# Posibus_proto.net
KiCad netlist of a schematic drawn in EAGLE
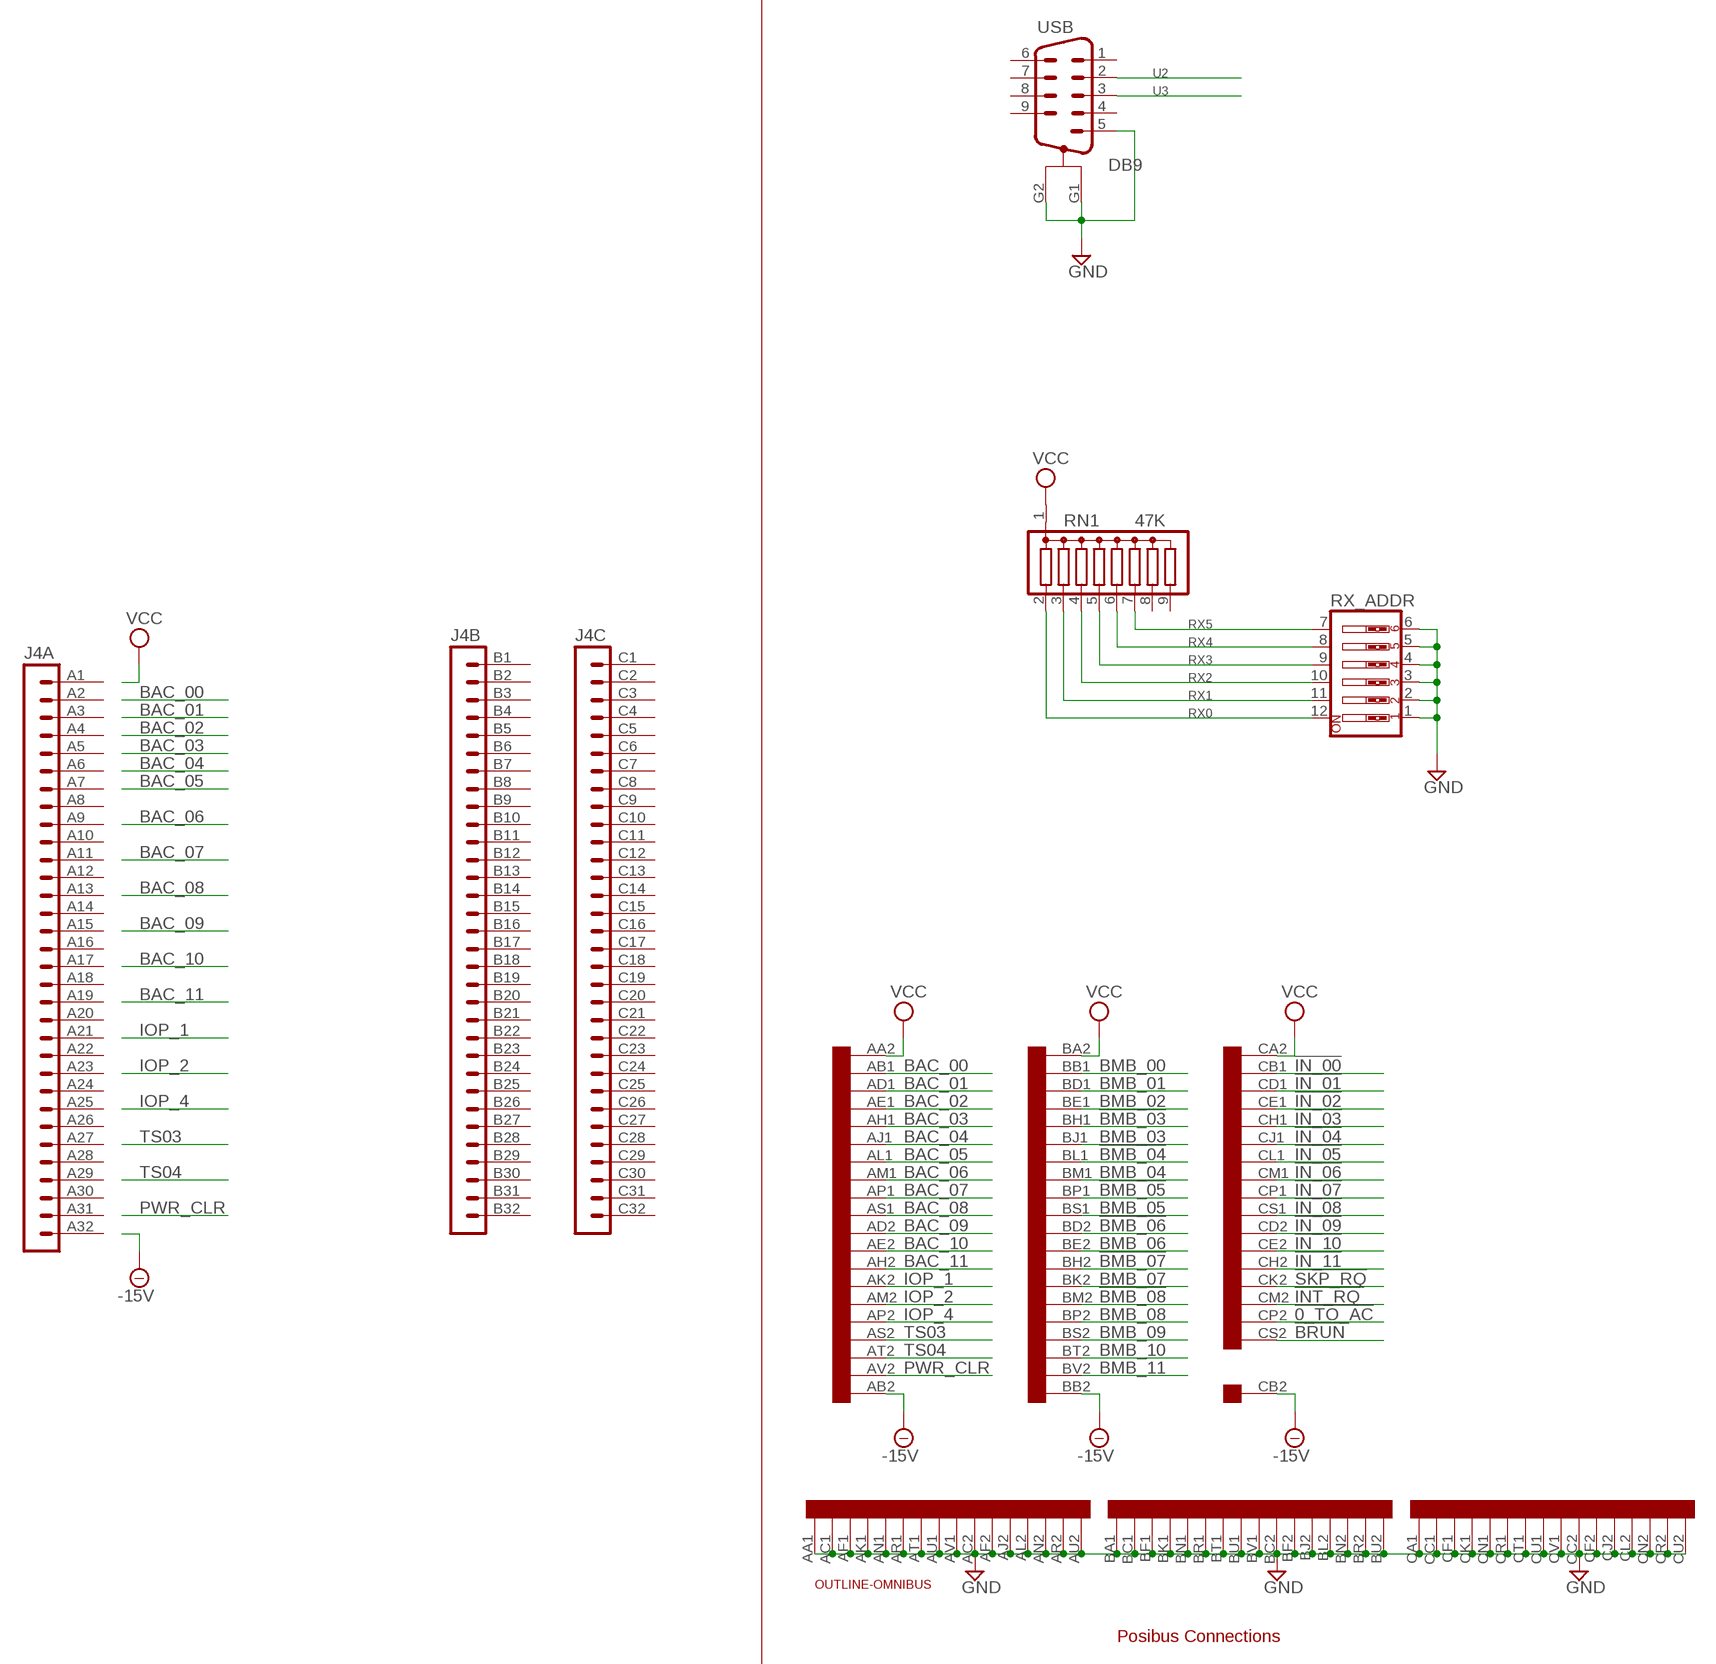
[diagram p0: schematic, sheet 1, part 1 of 2]
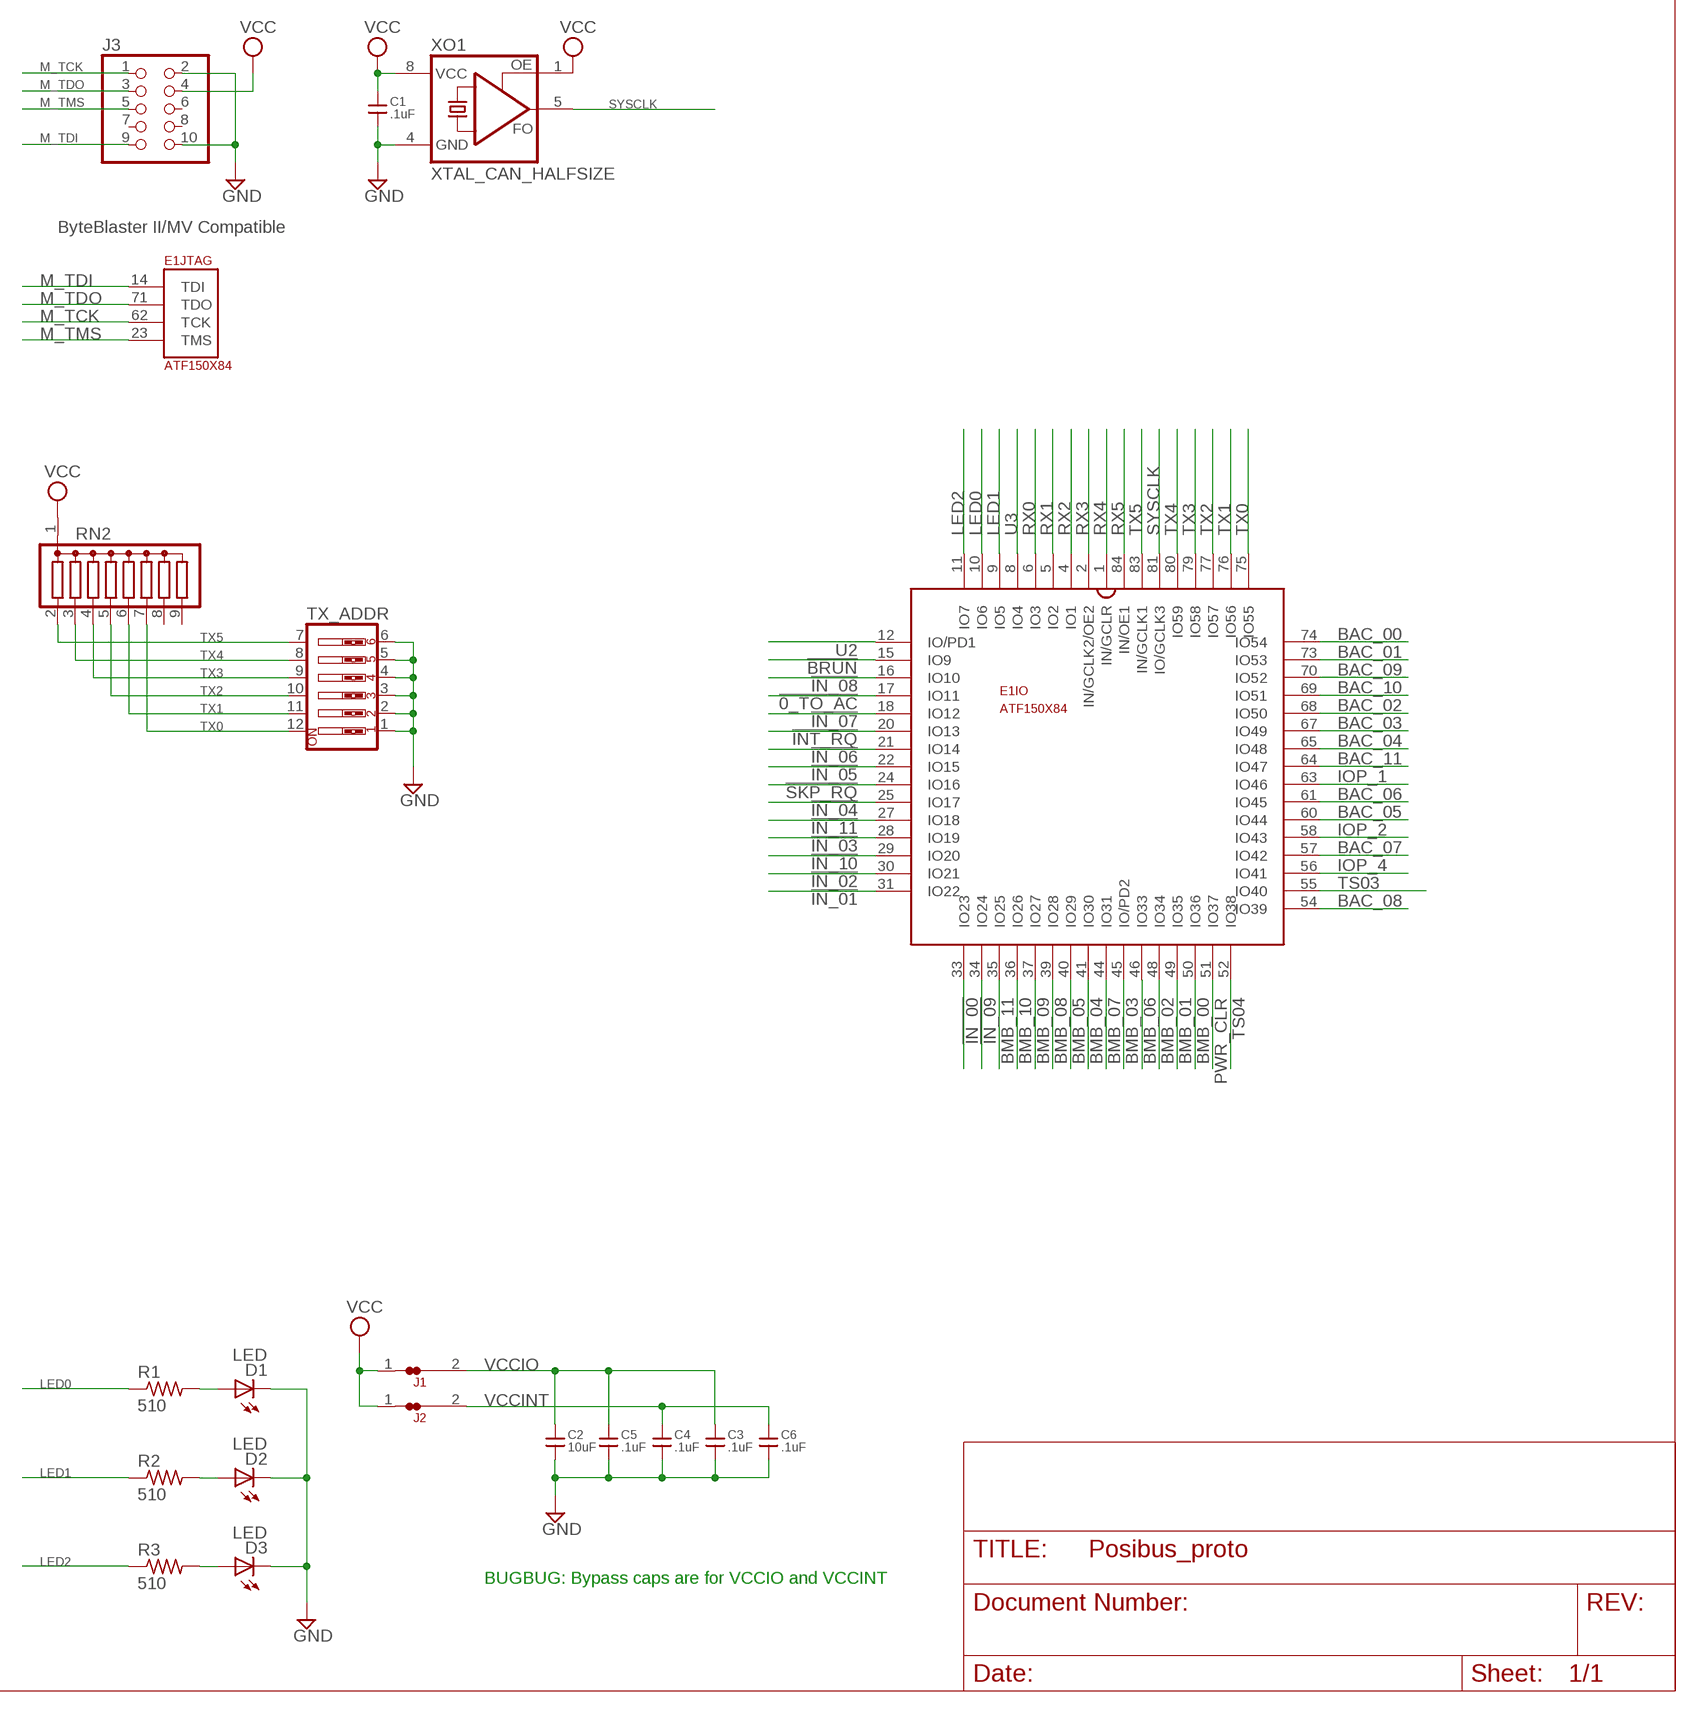
[diagram p1: schematic, sheet 1, part 2 of 2]

(export (version "E")
  (design (tool "Eeschema 10.0.6"))
  (components
    (comp (ref "C1")
      (value ".1uF")
      (footprint "eagle-import:C_TH_5MM")
      (libsource (lib "eagle-import") (part "C_US"))
    )
    (comp (ref "C2")
      (value "10uF")
      (footprint "eagle-import:C_TH_5MM")
      (libsource (lib "eagle-import") (part "C_US"))
    )
    (comp (ref "C3")
      (value ".1uF")
      (footprint "eagle-import:C_TH_5MM")
      (libsource (lib "eagle-import") (part "C_US"))
    )
    (comp (ref "C4")
      (value ".1uF")
      (footprint "eagle-import:C_TH_5MM")
      (libsource (lib "eagle-import") (part "C_US"))
    )
    (comp (ref "C5")
      (value ".1uF")
      (footprint "eagle-import:C_TH_5MM")
      (libsource (lib "eagle-import") (part "C_US"))
    )
    (comp (ref "C6")
      (value ".1uF")
      (footprint "eagle-import:C_TH_5MM")
      (libsource (lib "eagle-import") (part "C_US"))
    )
    (comp (ref "D1")
      (value "LED")
      (footprint "eagle-import:LED_TH_3MM")
      (libsource (lib "eagle-import") (part "LED"))
    )
    (comp (ref "D2")
      (value "LED")
      (footprint "eagle-import:LED_TH_3MM")
      (libsource (lib "eagle-import") (part "LED"))
    )
    (comp (ref "D3")
      (value "LED")
      (footprint "eagle-import:LED_TH_3MM")
      (libsource (lib "eagle-import") (part "LED"))
    )
    (comp (ref "E1")
      (value "ATF150X84")
      (footprint "eagle-import:S84")
      (libsource (lib "eagle-import") (part "ATF150X84"))
    )
    (comp (ref "J1")
      (value "JUMPER-NC1")
      (footprint "eagle-import:NC1")
      (libsource (lib "eagle-import") (part "JUMPER-NC1"))
    )
    (comp (ref "J2")
      (value "JUMPER-NC1")
      (footprint "eagle-import:NC1")
      (libsource (lib "eagle-import") (part "JUMPER-NC1"))
    )
    (comp (ref "J3")
      (value "HDR_2X5\"")
      (footprint "eagle-import:HDR_2X5")
      (libsource (lib "eagle-import") (part "HDR_2X5{dblquote}"))
    )
    (comp (ref "J4")
      (value "VG96-3B")
      (footprint "eagle-import:VG96B")
      (libsource (lib "eagle-import") (part "VG96-3B"))
    )
    (comp (ref "R1")
      (value "510")
      (footprint "eagle-import:R_204_7")
      (libsource (lib "eagle-import") (part "R_US"))
    )
    (comp (ref "R2")
      (value "510")
      (footprint "eagle-import:R_204_7")
      (libsource (lib "eagle-import") (part "R_US"))
    )
    (comp (ref "R3")
      (value "510")
      (footprint "eagle-import:R_204_7")
      (libsource (lib "eagle-import") (part "R_US"))
    )
    (comp (ref "RN1")
      (value "47K")
      (footprint "eagle-import:SIL9")
      (libsource (lib "eagle-import") (part "G08R"))
    )
    (comp (ref "RN2")
      (value "G08R")
      (footprint "eagle-import:SIL9")
      (libsource (lib "eagle-import") (part "G08R"))
    )
    (comp (ref "RX_ADDR")
      (value "SW_DIP-6")
      (footprint "eagle-import:EDG-06")
      (libsource (lib "eagle-import") (part "SW_DIP-6"))
    )
    (comp (ref "TX_ADDR")
      (value "SW_DIP-6")
      (footprint "eagle-import:EDG-06")
      (libsource (lib "eagle-import") (part "SW_DIP-6"))
    )
    (comp (ref "U$1")
      (value "QUAD")
      (footprint "eagle-import:EDGE-CON8")
      (libsource (lib "eagle-import") (part "QUAD"))
    )
    (comp (ref "U$2")
      (value "OUTLINE-OMNIBUS")
      (footprint "eagle-import:OMNIBUS")
      (libsource (lib "eagle-import") (part "OUTLINE-OMNIBUS"))
    )
    (comp (ref "USB")
      (value "DB9")
      (footprint "eagle-import:AMP_DB-9RA")
      (fields (field (name "MANF") "TE/AMP"))
      (libsource (lib "eagle-import") (part "DB9"))
    )
    (comp (ref "XO1")
      (value "XTAL_CAN_HALFSIZE")
      (footprint "eagle-import:XTAL_CAN_HALFSIZE")
      (libsource (lib "eagle-import") (part "XTAL_CAN_HALFSIZE"))
    )
  )
  (nets
    (net (code "1") (name "-15V") (class "Default")
      (node (ref "U$1") (pin "AB2") (pinfunction "1_AB2") (pintype "bidirectional"))
      (node (ref "U$1") (pin "BB2") (pinfunction "1_BB2") (pintype "bidirectional"))
      (node (ref "U$1") (pin "CB2") (pinfunction "1_CB2") (pintype "bidirectional"))
    )
    (net (code "2") (name "/BAC_00") (class "Default")
      (node (ref "E1") (pin "74") (pinfunction "IO54_74") (pintype "bidirectional"))
      (node (ref "U$1") (pin "AB1") (pinfunction "1_AB1") (pintype "bidirectional"))
    )
    (net (code "3") (name "/BAC_01") (class "Default")
      (node (ref "E1") (pin "73") (pinfunction "IO53_73") (pintype "bidirectional"))
      (node (ref "U$1") (pin "AD1") (pinfunction "1_AD1") (pintype "bidirectional"))
    )
    (net (code "4") (name "/BAC_02") (class "Default")
      (node (ref "E1") (pin "68") (pinfunction "IO50_68") (pintype "bidirectional"))
      (node (ref "U$1") (pin "AE1") (pinfunction "1_AE1") (pintype "bidirectional"))
    )
    (net (code "5") (name "/BAC_03") (class "Default")
      (node (ref "E1") (pin "67") (pinfunction "IO49_67") (pintype "bidirectional"))
      (node (ref "U$1") (pin "AH1") (pinfunction "1_AH1") (pintype "bidirectional"))
    )
    (net (code "6") (name "/BAC_04") (class "Default")
      (node (ref "E1") (pin "65") (pinfunction "IO48_65") (pintype "bidirectional"))
      (node (ref "U$1") (pin "AJ1") (pinfunction "1_AJ1") (pintype "bidirectional"))
    )
    (net (code "7") (name "/BAC_05") (class "Default")
      (node (ref "E1") (pin "60") (pinfunction "IO44_60") (pintype "bidirectional"))
      (node (ref "U$1") (pin "AL1") (pinfunction "1_AL1") (pintype "bidirectional"))
    )
    (net (code "8") (name "/BAC_06") (class "Default")
      (node (ref "E1") (pin "61") (pinfunction "IO45_61") (pintype "bidirectional"))
      (node (ref "U$1") (pin "AM1") (pinfunction "1_AM1") (pintype "bidirectional"))
    )
    (net (code "9") (name "/BAC_07") (class "Default")
      (node (ref "E1") (pin "57") (pinfunction "IO42_57") (pintype "bidirectional"))
      (node (ref "U$1") (pin "AP1") (pinfunction "1_AP1") (pintype "bidirectional"))
    )
    (net (code "10") (name "/BAC_08") (class "Default")
      (node (ref "E1") (pin "54") (pinfunction "IO39_54") (pintype "bidirectional"))
      (node (ref "U$1") (pin "AS1") (pinfunction "1_AS1") (pintype "bidirectional"))
    )
    (net (code "11") (name "/BAC_09") (class "Default")
      (node (ref "E1") (pin "70") (pinfunction "IO52_70") (pintype "bidirectional"))
      (node (ref "U$1") (pin "AD2") (pinfunction "1_AD2") (pintype "bidirectional"))
    )
    (net (code "12") (name "/BAC_10") (class "Default")
      (node (ref "E1") (pin "69") (pinfunction "IO51_69") (pintype "bidirectional"))
      (node (ref "U$1") (pin "AE2") (pinfunction "1_AE2") (pintype "bidirectional"))
    )
    (net (code "13") (name "/BAC_11") (class "Default")
      (node (ref "E1") (pin "64") (pinfunction "IO47_64") (pintype "bidirectional"))
      (node (ref "U$1") (pin "AH2") (pinfunction "1_AH2") (pintype "bidirectional"))
    )
    (net (code "14") (name "/BMB_00") (class "Default")
      (node (ref "E1") (pin "50") (pinfunction "IO36_50") (pintype "bidirectional"))
      (node (ref "U$1") (pin "BB1") (pinfunction "1_BB1") (pintype "bidirectional"))
    )
    (net (code "15") (name "/BMB_01") (class "Default")
      (node (ref "E1") (pin "49") (pinfunction "IO35_49") (pintype "bidirectional"))
      (node (ref "U$1") (pin "BD1") (pinfunction "1_BD1") (pintype "bidirectional"))
    )
    (net (code "16") (name "/BMB_02") (class "Default")
      (node (ref "E1") (pin "48") (pinfunction "IO34_48") (pintype "bidirectional"))
      (node (ref "U$1") (pin "BE1") (pinfunction "1_BE1") (pintype "bidirectional"))
    )
    (net (code "17") (name "/BMB_03") (class "Default")
      (node (ref "E1") (pin "45") (pinfunction "IO/PD2_45") (pintype "bidirectional"))
      (node (ref "U$1") (pin "BJ1") (pinfunction "1_BJ1") (pintype "bidirectional"))
    )
    (net (code "18") (name "/BMB_04") (class "Default")
      (node (ref "E1") (pin "41") (pinfunction "IO30_41") (pintype "bidirectional"))
      (node (ref "U$1") (pin "BM1") (pinfunction "1_BM1") (pintype "bidirectional"))
    )
    (net (code "19") (name "/BMB_05") (class "Default")
      (node (ref "E1") (pin "40") (pinfunction "IO29_40") (pintype "bidirectional"))
      (node (ref "U$1") (pin "BS1") (pinfunction "1_BS1") (pintype "bidirectional"))
    )
    (net (code "20") (name "/BMB_06") (class "Default")
      (node (ref "E1") (pin "46") (pinfunction "IO33_46") (pintype "bidirectional"))
      (node (ref "U$1") (pin "BE2") (pinfunction "1_BE2") (pintype "bidirectional"))
    )
    (net (code "21") (name "/BMB_07") (class "Default")
      (node (ref "E1") (pin "44") (pinfunction "IO31_44") (pintype "bidirectional"))
      (node (ref "U$1") (pin "BK2") (pinfunction "1_BK2") (pintype "bidirectional"))
    )
    (net (code "22") (name "/BMB_08") (class "Default")
      (node (ref "E1") (pin "39") (pinfunction "IO28_39") (pintype "bidirectional"))
      (node (ref "U$1") (pin "BP2") (pinfunction "1_BP2") (pintype "bidirectional"))
    )
    (net (code "23") (name "/BMB_09") (class "Default")
      (node (ref "E1") (pin "37") (pinfunction "IO27_37") (pintype "bidirectional"))
      (node (ref "U$1") (pin "BS2") (pinfunction "1_BS2") (pintype "bidirectional"))
    )
    (net (code "24") (name "/BMB_10") (class "Default")
      (node (ref "E1") (pin "36") (pinfunction "IO26_36") (pintype "bidirectional"))
      (node (ref "U$1") (pin "BT2") (pinfunction "1_BT2") (pintype "bidirectional"))
    )
    (net (code "25") (name "/BMB_11") (class "Default")
      (node (ref "E1") (pin "35") (pinfunction "IO25_35") (pintype "bidirectional"))
      (node (ref "U$1") (pin "BV2") (pinfunction "1_BV2") (pintype "bidirectional"))
    )
    (net (code "26") (name "/IOP_1") (class "Default")
      (node (ref "E1") (pin "63") (pinfunction "IO46_63") (pintype "bidirectional"))
      (node (ref "U$1") (pin "AK2") (pinfunction "1_AK2") (pintype "bidirectional"))
    )
    (net (code "27") (name "/IOP_2") (class "Default")
      (node (ref "E1") (pin "58") (pinfunction "IO43_58") (pintype "bidirectional"))
      (node (ref "U$1") (pin "AM2") (pinfunction "1_AM2") (pintype "bidirectional"))
    )
    (net (code "28") (name "/IOP_4") (class "Default")
      (node (ref "E1") (pin "56") (pinfunction "IO41_56") (pintype "bidirectional"))
      (node (ref "U$1") (pin "AP2") (pinfunction "1_AP2") (pintype "bidirectional"))
    )
    (net (code "29") (name "/LED0") (class "Default")
      (node (ref "E1") (pin "10") (pinfunction "IO6_10") (pintype "bidirectional"))
      (node (ref "R1") (pin "1") (pinfunction "1_1") (pintype "passive"))
    )
    (net (code "30") (name "/LED1") (class "Default")
      (node (ref "E1") (pin "9") (pinfunction "IO5_9") (pintype "bidirectional"))
      (node (ref "R2") (pin "1") (pinfunction "1_1") (pintype "passive"))
    )
    (net (code "31") (name "/LED2") (class "Default")
      (node (ref "E1") (pin "11") (pinfunction "IO7_11") (pintype "bidirectional"))
      (node (ref "R3") (pin "1") (pinfunction "1_1") (pintype "passive"))
    )
    (net (code "32") (name "/M_TCK") (class "Default")
      (node (ref "E1") (pin "62") (pinfunction "TCK_62") (pintype "bidirectional"))
      (node (ref "J3") (pin "1") (pinfunction "1_1") (pintype "passive"))
    )
    (net (code "33") (name "/M_TDI") (class "Default")
      (node (ref "E1") (pin "14") (pinfunction "TDI_14") (pintype "bidirectional"))
      (node (ref "J3") (pin "9") (pinfunction "9_9") (pintype "passive"))
    )
    (net (code "34") (name "/M_TDO") (class "Default")
      (node (ref "E1") (pin "71") (pinfunction "TDO_71") (pintype "bidirectional"))
      (node (ref "J3") (pin "3") (pinfunction "3_3") (pintype "passive"))
    )
    (net (code "35") (name "/M_TMS") (class "Default")
      (node (ref "E1") (pin "23") (pinfunction "TMS_23") (pintype "bidirectional"))
      (node (ref "J3") (pin "5") (pinfunction "5_5") (pintype "passive"))
    )
    (net (code "36") (name "/PWR_CLR") (class "Default")
      (node (ref "E1") (pin "51") (pinfunction "IO37_51") (pintype "bidirectional"))
      (node (ref "U$1") (pin "AV2") (pinfunction "1_AV2") (pintype "bidirectional"))
    )
    (net (code "37") (name "/RX0") (class "Default")
      (node (ref "E1") (pin "6") (pinfunction "IO3_6") (pintype "bidirectional"))
      (node (ref "RN1") (pin "2") (pinfunction "2_2") (pintype "passive"))
      (node (ref "RX_ADDR") (pin "12") (pinfunction "12_12") (pintype "passive"))
    )
    (net (code "38") (name "/RX1") (class "Default")
      (node (ref "E1") (pin "5") (pinfunction "IO2_5") (pintype "bidirectional"))
      (node (ref "RN1") (pin "3") (pinfunction "3_3") (pintype "passive"))
      (node (ref "RX_ADDR") (pin "11") (pinfunction "11_11") (pintype "passive"))
    )
    (net (code "39") (name "/RX2") (class "Default")
      (node (ref "E1") (pin "4") (pinfunction "IO1_4") (pintype "bidirectional"))
      (node (ref "RN1") (pin "4") (pinfunction "4_4") (pintype "passive"))
      (node (ref "RX_ADDR") (pin "10") (pinfunction "10_10") (pintype "passive"))
    )
    (net (code "40") (name "/RX3") (class "Default")
      (node (ref "E1") (pin "2") (pinfunction "IN/GCLK2/OE2_2") (pintype "input"))
      (node (ref "RN1") (pin "5") (pinfunction "5_5") (pintype "passive"))
      (node (ref "RX_ADDR") (pin "9") (pinfunction "9_9") (pintype "passive"))
    )
    (net (code "41") (name "/RX4") (class "Default")
      (node (ref "E1") (pin "1") (pinfunction "IN/GCLR_1") (pintype "input"))
      (node (ref "RN1") (pin "6") (pinfunction "6_6") (pintype "passive"))
      (node (ref "RX_ADDR") (pin "8") (pinfunction "8_8") (pintype "passive"))
    )
    (net (code "42") (name "/RX5") (class "Default")
      (node (ref "E1") (pin "84") (pinfunction "IN/OE1_84") (pintype "input"))
      (node (ref "RN1") (pin "7") (pinfunction "7_7") (pintype "passive"))
      (node (ref "RX_ADDR") (pin "7") (pinfunction "7_7") (pintype "passive"))
    )
    (net (code "43") (name "/SYSCLK") (class "Default")
      (node (ref "E1") (pin "81") (pinfunction "IO/GCLK3_81") (pintype "bidirectional"))
      (node (ref "XO1") (pin "5") (pinfunction "FO_5") (pintype "output"))
    )
    (net (code "44") (name "/TS03") (class "Default")
      (node (ref "E1") (pin "55") (pinfunction "IO40_55") (pintype "bidirectional"))
      (node (ref "U$1") (pin "AS2") (pinfunction "1_AS2") (pintype "bidirectional"))
    )
    (net (code "45") (name "/TS04") (class "Default")
      (node (ref "E1") (pin "52") (pinfunction "IO38_52") (pintype "bidirectional"))
      (node (ref "U$1") (pin "AT2") (pinfunction "1_AT2") (pintype "bidirectional"))
    )
    (net (code "46") (name "/TX0") (class "Default")
      (node (ref "E1") (pin "75") (pinfunction "IO55_75") (pintype "bidirectional"))
      (node (ref "RN2") (pin "7") (pinfunction "7_7") (pintype "passive"))
      (node (ref "TX_ADDR") (pin "12") (pinfunction "12_12") (pintype "passive"))
    )
    (net (code "47") (name "/TX1") (class "Default")
      (node (ref "E1") (pin "76") (pinfunction "IO56_76") (pintype "bidirectional"))
      (node (ref "RN2") (pin "6") (pinfunction "6_6") (pintype "passive"))
      (node (ref "TX_ADDR") (pin "11") (pinfunction "11_11") (pintype "passive"))
    )
    (net (code "48") (name "/TX2") (class "Default")
      (node (ref "E1") (pin "77") (pinfunction "IO57_77") (pintype "bidirectional"))
      (node (ref "RN2") (pin "5") (pinfunction "5_5") (pintype "passive"))
      (node (ref "TX_ADDR") (pin "10") (pinfunction "10_10") (pintype "passive"))
    )
    (net (code "49") (name "/TX3") (class "Default")
      (node (ref "E1") (pin "79") (pinfunction "IO58_79") (pintype "bidirectional"))
      (node (ref "RN2") (pin "4") (pinfunction "4_4") (pintype "passive"))
      (node (ref "TX_ADDR") (pin "9") (pinfunction "9_9") (pintype "passive"))
    )
    (net (code "50") (name "/TX4") (class "Default")
      (node (ref "E1") (pin "80") (pinfunction "IO59_80") (pintype "bidirectional"))
      (node (ref "RN2") (pin "3") (pinfunction "3_3") (pintype "passive"))
      (node (ref "TX_ADDR") (pin "8") (pinfunction "8_8") (pintype "passive"))
    )
    (net (code "51") (name "/TX5") (class "Default")
      (node (ref "E1") (pin "83") (pinfunction "IN/GCLK1_83") (pintype "input"))
      (node (ref "RN2") (pin "2") (pinfunction "2_2") (pintype "passive"))
      (node (ref "TX_ADDR") (pin "7") (pinfunction "7_7") (pintype "passive"))
    )
    (net (code "52") (name "/U2") (class "Default")
      (node (ref "E1") (pin "12") (pinfunction "IO/PD1_12") (pintype "bidirectional"))
      (node (ref "USB") (pin "2") (pinfunction "2_2") (pintype "passive"))
    )
    (net (code "53") (name "/U3") (class "Default")
      (node (ref "E1") (pin "8") (pinfunction "IO4_8") (pintype "bidirectional"))
      (node (ref "USB") (pin "3") (pinfunction "3_3") (pintype "passive"))
    )
    (net (code "54") (name "/VCCINT") (class "Default")
      (node (ref "C4") (pin "1") (pinfunction "1_1") (pintype "passive"))
      (node (ref "C6") (pin "1") (pinfunction "1_1") (pintype "passive"))
      (node (ref "J2") (pin "2") (pinfunction "2_2") (pintype "bidirectional"))
    )
    (net (code "55") (name "/VCCIO") (class "Default")
      (node (ref "C2") (pin "1") (pinfunction "1_1") (pintype "passive"))
      (node (ref "C3") (pin "1") (pinfunction "1_1") (pintype "passive"))
      (node (ref "C5") (pin "1") (pinfunction "1_1") (pintype "passive"))
      (node (ref "J1") (pin "2") (pinfunction "2_2") (pintype "bidirectional"))
    )
    (net (code "56") (name "/~{0_TO_AC}") (class "Default")
      (node (ref "E1") (pin "17") (pinfunction "IO11_17") (pintype "bidirectional"))
      (node (ref "U$1") (pin "CP2") (pinfunction "1_CP2") (pintype "bidirectional"))
    )
    (net (code "57") (name "/~{BMB_03}") (class "Default")
      (node (ref "U$1") (pin "BH1") (pinfunction "1_BH1") (pintype "bidirectional"))
    )
    (net (code "58") (name "/~{BMB_04}") (class "Default")
      (node (ref "U$1") (pin "BL1") (pinfunction "1_BL1") (pintype "bidirectional"))
    )
    (net (code "59") (name "/~{BMB_05}") (class "Default")
      (node (ref "U$1") (pin "BP1") (pinfunction "1_BP1") (pintype "bidirectional"))
    )
    (net (code "60") (name "/~{BMB_06}") (class "Default")
      (node (ref "U$1") (pin "BD2") (pinfunction "1_BD2") (pintype "bidirectional"))
    )
    (net (code "61") (name "/~{BMB_07}") (class "Default")
      (node (ref "U$1") (pin "BH2") (pinfunction "1_BH2") (pintype "bidirectional"))
    )
    (net (code "62") (name "/~{BMB_08}") (class "Default")
      (node (ref "U$1") (pin "BM2") (pinfunction "1_BM2") (pintype "bidirectional"))
    )
    (net (code "63") (name "/~{BRUN}") (class "Default")
      (node (ref "E1") (pin "15") (pinfunction "IO9_15") (pintype "bidirectional"))
      (node (ref "U$1") (pin "CS2") (pinfunction "1_CS2") (pintype "bidirectional"))
    )
    (net (code "64") (name "/~{INT_RQ}") (class "Default")
      (node (ref "E1") (pin "20") (pinfunction "IO13_20") (pintype "bidirectional"))
      (node (ref "U$1") (pin "CM2") (pinfunction "1_CM2") (pintype "bidirectional"))
    )
    (net (code "65") (name "/~{IN_00}") (class "Default")
      (node (ref "E1") (pin "33") (pinfunction "IO23_33") (pintype "bidirectional"))
      (node (ref "U$1") (pin "CB1") (pinfunction "1_CB1") (pintype "bidirectional"))
    )
    (net (code "66") (name "/~{IN_01}") (class "Default")
      (node (ref "E1") (pin "31") (pinfunction "IO22_31") (pintype "bidirectional"))
      (node (ref "U$1") (pin "CD1") (pinfunction "1_CD1") (pintype "bidirectional"))
    )
    (net (code "67") (name "/~{IN_02}") (class "Default")
      (node (ref "E1") (pin "30") (pinfunction "IO21_30") (pintype "bidirectional"))
      (node (ref "U$1") (pin "CE1") (pinfunction "1_CE1") (pintype "bidirectional"))
    )
    (net (code "68") (name "/~{IN_03}") (class "Default")
      (node (ref "E1") (pin "28") (pinfunction "IO19_28") (pintype "bidirectional"))
      (node (ref "U$1") (pin "CH1") (pinfunction "1_CH1") (pintype "bidirectional"))
    )
    (net (code "69") (name "/~{IN_04}") (class "Default")
      (node (ref "E1") (pin "25") (pinfunction "IO17_25") (pintype "bidirectional"))
      (node (ref "U$1") (pin "CJ1") (pinfunction "1_CJ1") (pintype "bidirectional"))
    )
    (net (code "70") (name "/~{IN_05}") (class "Default")
      (node (ref "E1") (pin "22") (pinfunction "IO15_22") (pintype "bidirectional"))
      (node (ref "U$1") (pin "CL1") (pinfunction "1_CL1") (pintype "bidirectional"))
    )
    (net (code "71") (name "/~{IN_06}") (class "Default")
      (node (ref "E1") (pin "21") (pinfunction "IO14_21") (pintype "bidirectional"))
      (node (ref "U$1") (pin "CM1") (pinfunction "1_CM1") (pintype "bidirectional"))
    )
    (net (code "72") (name "/~{IN_07}") (class "Default")
      (node (ref "E1") (pin "18") (pinfunction "IO12_18") (pintype "bidirectional"))
      (node (ref "U$1") (pin "CP1") (pinfunction "1_CP1") (pintype "bidirectional"))
    )
    (net (code "73") (name "/~{IN_08}") (class "Default")
      (node (ref "E1") (pin "16") (pinfunction "IO10_16") (pintype "bidirectional"))
      (node (ref "U$1") (pin "CS1") (pinfunction "1_CS1") (pintype "bidirectional"))
    )
    (net (code "74") (name "/~{IN_09}") (class "Default")
      (node (ref "E1") (pin "34") (pinfunction "IO24_34") (pintype "bidirectional"))
      (node (ref "U$1") (pin "CD2") (pinfunction "1_CD2") (pintype "bidirectional"))
    )
    (net (code "75") (name "/~{IN_10}") (class "Default")
      (node (ref "E1") (pin "29") (pinfunction "IO20_29") (pintype "bidirectional"))
      (node (ref "U$1") (pin "CE2") (pinfunction "1_CE2") (pintype "bidirectional"))
    )
    (net (code "76") (name "/~{IN_11}") (class "Default")
      (node (ref "E1") (pin "27") (pinfunction "IO18_27") (pintype "bidirectional"))
      (node (ref "U$1") (pin "CH2") (pinfunction "1_CH2") (pintype "bidirectional"))
    )
    (net (code "77") (name "/~{SKP_RQ}") (class "Default")
      (node (ref "E1") (pin "24") (pinfunction "IO16_24") (pintype "bidirectional"))
      (node (ref "U$1") (pin "CK2") (pinfunction "1_CK2") (pintype "bidirectional"))
    )
    (net (code "78") (name "GND") (class "Default")
      (node (ref "C1") (pin "2") (pinfunction "2_2") (pintype "passive"))
      (node (ref "C2") (pin "2") (pinfunction "2_2") (pintype "passive"))
      (node (ref "C3") (pin "2") (pinfunction "2_2") (pintype "passive"))
      (node (ref "C4") (pin "2") (pinfunction "2_2") (pintype "passive"))
      (node (ref "C5") (pin "2") (pinfunction "2_2") (pintype "passive"))
      (node (ref "C6") (pin "2") (pinfunction "2_2") (pintype "passive"))
      (node (ref "D1") (pin "K") (pinfunction "C_K") (pintype "passive"))
      (node (ref "D2") (pin "K") (pinfunction "C_K") (pintype "passive"))
      (node (ref "D3") (pin "K") (pinfunction "C_K") (pintype "passive"))
      (node (ref "J3") (pin "10") (pinfunction "10_10") (pintype "passive"))
      (node (ref "J3") (pin "2") (pinfunction "2_2") (pintype "passive"))
      (node (ref "RX_ADDR") (pin "1") (pinfunction "1_1") (pintype "passive"))
      (node (ref "RX_ADDR") (pin "2") (pinfunction "2_2") (pintype "passive"))
      (node (ref "RX_ADDR") (pin "3") (pinfunction "3_3") (pintype "passive"))
      (node (ref "RX_ADDR") (pin "4") (pinfunction "4_4") (pintype "passive"))
      (node (ref "RX_ADDR") (pin "5") (pinfunction "5_5") (pintype "passive"))
      (node (ref "RX_ADDR") (pin "6") (pinfunction "6_6") (pintype "passive"))
      (node (ref "TX_ADDR") (pin "1") (pinfunction "1_1") (pintype "passive"))
      (node (ref "TX_ADDR") (pin "2") (pinfunction "2_2") (pintype "passive"))
      (node (ref "TX_ADDR") (pin "3") (pinfunction "3_3") (pintype "passive"))
      (node (ref "TX_ADDR") (pin "4") (pinfunction "4_4") (pintype "passive"))
      (node (ref "TX_ADDR") (pin "5") (pinfunction "5_5") (pintype "passive"))
      (node (ref "TX_ADDR") (pin "6") (pinfunction "6_6") (pintype "passive"))
      (node (ref "U$1") (pin "AA1") (pinfunction "1_AA1") (pintype "bidirectional"))
      (node (ref "U$1") (pin "AC1") (pinfunction "1_AC1") (pintype "bidirectional"))
      (node (ref "U$1") (pin "AC2") (pinfunction "1_AC2") (pintype "bidirectional"))
      (node (ref "U$1") (pin "AF1") (pinfunction "1_AF1") (pintype "bidirectional"))
      (node (ref "U$1") (pin "AF2") (pinfunction "1_AF2") (pintype "bidirectional"))
      (node (ref "U$1") (pin "AJ2") (pinfunction "1_AJ2") (pintype "bidirectional"))
      (node (ref "U$1") (pin "AK1") (pinfunction "1_AK1") (pintype "bidirectional"))
      (node (ref "U$1") (pin "AL2") (pinfunction "1_AL2") (pintype "bidirectional"))
      (node (ref "U$1") (pin "AN1") (pinfunction "1_AN1") (pintype "bidirectional"))
      (node (ref "U$1") (pin "AN2") (pinfunction "1_AN2") (pintype "bidirectional"))
      (node (ref "U$1") (pin "AR1") (pinfunction "1_AR1") (pintype "bidirectional"))
      (node (ref "U$1") (pin "AR2") (pinfunction "1_AR2") (pintype "bidirectional"))
      (node (ref "U$1") (pin "AT1") (pinfunction "1_AT1") (pintype "bidirectional"))
      (node (ref "U$1") (pin "AU1") (pinfunction "1_AU1") (pintype "bidirectional"))
      (node (ref "U$1") (pin "AU2") (pinfunction "1_AU2") (pintype "bidirectional"))
      (node (ref "U$1") (pin "AV1") (pinfunction "1_AV1") (pintype "bidirectional"))
      (node (ref "U$1") (pin "BA1") (pinfunction "1_BA1") (pintype "bidirectional"))
      (node (ref "U$1") (pin "BC1") (pinfunction "1_BC1") (pintype "bidirectional"))
      (node (ref "U$1") (pin "BC2") (pinfunction "1_BC2") (pintype "bidirectional"))
      (node (ref "U$1") (pin "BF1") (pinfunction "1_BF1") (pintype "bidirectional"))
      (node (ref "U$1") (pin "BF2") (pinfunction "1_BF2") (pintype "bidirectional"))
      (node (ref "U$1") (pin "BJ2") (pinfunction "1_BJ2") (pintype "bidirectional"))
      (node (ref "U$1") (pin "BK1") (pinfunction "1_BK1") (pintype "bidirectional"))
      (node (ref "U$1") (pin "BL2") (pinfunction "1_BL2") (pintype "bidirectional"))
      (node (ref "U$1") (pin "BN1") (pinfunction "1_BN1") (pintype "bidirectional"))
      (node (ref "U$1") (pin "BN2") (pinfunction "1_BN2") (pintype "bidirectional"))
      (node (ref "U$1") (pin "BR1") (pinfunction "1_BR1") (pintype "bidirectional"))
      (node (ref "U$1") (pin "BR2") (pinfunction "1_BR2") (pintype "bidirectional"))
      (node (ref "U$1") (pin "BT1") (pinfunction "1_BT1") (pintype "bidirectional"))
      (node (ref "U$1") (pin "BU1") (pinfunction "1_BU1") (pintype "bidirectional"))
      (node (ref "U$1") (pin "BU2") (pinfunction "1_BU2") (pintype "bidirectional"))
      (node (ref "U$1") (pin "BV1") (pinfunction "1_BV1") (pintype "bidirectional"))
      (node (ref "U$1") (pin "CA1") (pinfunction "1_CA1") (pintype "bidirectional"))
      (node (ref "U$1") (pin "CC1") (pinfunction "1_CC1") (pintype "bidirectional"))
      (node (ref "U$1") (pin "CC2") (pinfunction "1_CC2") (pintype "bidirectional"))
      (node (ref "U$1") (pin "CF1") (pinfunction "1_CF1") (pintype "bidirectional"))
      (node (ref "U$1") (pin "CF2") (pinfunction "1_CF2") (pintype "bidirectional"))
      (node (ref "U$1") (pin "CJ2") (pinfunction "1_CJ2") (pintype "bidirectional"))
      (node (ref "U$1") (pin "CK1") (pinfunction "1_CK1") (pintype "bidirectional"))
      (node (ref "U$1") (pin "CL2") (pinfunction "1_CL2") (pintype "bidirectional"))
      (node (ref "U$1") (pin "CN1") (pinfunction "1_CN1") (pintype "bidirectional"))
      (node (ref "U$1") (pin "CN2") (pinfunction "1_CN2") (pintype "bidirectional"))
      (node (ref "U$1") (pin "CR1") (pinfunction "1_CR1") (pintype "bidirectional"))
      (node (ref "U$1") (pin "CR2") (pinfunction "1_CR2") (pintype "bidirectional"))
      (node (ref "U$1") (pin "CT1") (pinfunction "1_CT1") (pintype "bidirectional"))
      (node (ref "U$1") (pin "CU1") (pinfunction "1_CU1") (pintype "bidirectional"))
      (node (ref "U$1") (pin "CU2") (pinfunction "1_CU2") (pintype "bidirectional"))
      (node (ref "U$1") (pin "CV1") (pinfunction "1_CV1") (pintype "bidirectional"))
      (node (ref "USB") (pin "5") (pinfunction "5_5") (pintype "passive"))
      (node (ref "USB") (pin "G1") (pinfunction "G1_G1") (pintype "passive"))
      (node (ref "USB") (pin "G2") (pinfunction "G2_G2") (pintype "passive"))
      (node (ref "XO1") (pin "4") (pinfunction "GND_4") (pintype "power_in"))
    )
    (net (code "79") (name "Net-(D1-PadA)") (class "Default")
      (node (ref "D1") (pin "A") (pinfunction "A_A") (pintype "passive"))
      (node (ref "R1") (pin "2") (pinfunction "2_2") (pintype "passive"))
    )
    (net (code "80") (name "Net-(D2-PadA)") (class "Default")
      (node (ref "D2") (pin "A") (pinfunction "A_A") (pintype "passive"))
      (node (ref "R2") (pin "2") (pinfunction "2_2") (pintype "passive"))
    )
    (net (code "81") (name "Net-(D3-PadA)") (class "Default")
      (node (ref "D3") (pin "A") (pinfunction "A_A") (pintype "passive"))
      (node (ref "R3") (pin "2") (pinfunction "2_2") (pintype "passive"))
    )
    (net (code "82") (name "VCC") (class "Default")
      (node (ref "C1") (pin "1") (pinfunction "1_1") (pintype "passive"))
      (node (ref "J1") (pin "1") (pinfunction "1_1") (pintype "bidirectional"))
      (node (ref "J2") (pin "1") (pinfunction "1_1") (pintype "bidirectional"))
      (node (ref "J3") (pin "4") (pinfunction "4_4") (pintype "passive"))
      (node (ref "RN1") (pin "1") (pinfunction "1_1") (pintype "passive"))
      (node (ref "RN2") (pin "1") (pinfunction "1_1") (pintype "passive"))
      (node (ref "U$1") (pin "AA2") (pinfunction "1_AA2") (pintype "bidirectional"))
      (node (ref "U$1") (pin "BA2") (pinfunction "1_BA2") (pintype "bidirectional"))
      (node (ref "U$1") (pin "CA2") (pinfunction "1_CA2") (pintype "bidirectional"))
      (node (ref "XO1") (pin "1") (pinfunction "OE_1") (pintype "input"))
      (node (ref "XO1") (pin "8") (pinfunction "VCC_8") (pintype "power_in"))
    )
    (net (code "83") (name "unconnected-(J3-Pad6)") (class "Default")
      (node (ref "J3") (pin "6") (pinfunction "6_6") (pintype "passive"))
    )
    (net (code "84") (name "unconnected-(J3-Pad7)") (class "Default")
      (node (ref "J3") (pin "7") (pinfunction "7_7") (pintype "passive"))
    )
    (net (code "85") (name "unconnected-(J3-Pad8)") (class "Default")
      (node (ref "J3") (pin "8") (pinfunction "8_8") (pintype "passive"))
    )
    (net (code "86") (name "unconnected-(J4A-1-PadA1)") (class "Default")
      (node (ref "J4") (pin "A1") (pinfunction "1_A1") (pintype "passive"))
    )
    (net (code "87") (name "unconnected-(J4A-2-PadA2)") (class "Default")
      (node (ref "J4") (pin "A2") (pinfunction "2_A2") (pintype "passive"))
    )
    (net (code "88") (name "unconnected-(J4A-3-PadA3)") (class "Default")
      (node (ref "J4") (pin "A3") (pinfunction "3_A3") (pintype "passive"))
    )
    (net (code "89") (name "unconnected-(J4A-4-PadA4)") (class "Default")
      (node (ref "J4") (pin "A4") (pinfunction "4_A4") (pintype "passive"))
    )
    (net (code "90") (name "unconnected-(J4A-5-PadA5)") (class "Default")
      (node (ref "J4") (pin "A5") (pinfunction "5_A5") (pintype "passive"))
    )
    (net (code "91") (name "unconnected-(J4A-6-PadA6)") (class "Default")
      (node (ref "J4") (pin "A6") (pinfunction "6_A6") (pintype "passive"))
    )
    (net (code "92") (name "unconnected-(J4A-7-PadA7)") (class "Default")
      (node (ref "J4") (pin "A7") (pinfunction "7_A7") (pintype "passive"))
    )
    (net (code "93") (name "unconnected-(J4A-8-PadA8)") (class "Default")
      (node (ref "J4") (pin "A8") (pinfunction "8_A8") (pintype "passive"))
    )
    (net (code "94") (name "unconnected-(J4A-9-PadA9)") (class "Default")
      (node (ref "J4") (pin "A9") (pinfunction "9_A9") (pintype "passive"))
    )
    (net (code "95") (name "unconnected-(J4A-10-PadA10)") (class "Default")
      (node (ref "J4") (pin "A10") (pinfunction "10_A10") (pintype "passive"))
    )
    (net (code "96") (name "unconnected-(J4A-11-PadA11)") (class "Default")
      (node (ref "J4") (pin "A11") (pinfunction "11_A11") (pintype "passive"))
    )
    (net (code "97") (name "unconnected-(J4A-12-PadA12)") (class "Default")
      (node (ref "J4") (pin "A12") (pinfunction "12_A12") (pintype "passive"))
    )
    (net (code "98") (name "unconnected-(J4A-13-PadA13)") (class "Default")
      (node (ref "J4") (pin "A13") (pinfunction "13_A13") (pintype "passive"))
    )
    (net (code "99") (name "unconnected-(J4A-14-PadA14)") (class "Default")
      (node (ref "J4") (pin "A14") (pinfunction "14_A14") (pintype "passive"))
    )
    (net (code "100") (name "unconnected-(J4A-15-PadA15)") (class "Default")
      (node (ref "J4") (pin "A15") (pinfunction "15_A15") (pintype "passive"))
    )
    (net (code "101") (name "unconnected-(J4A-16-PadA16)") (class "Default")
      (node (ref "J4") (pin "A16") (pinfunction "16_A16") (pintype "passive"))
    )
    (net (code "102") (name "unconnected-(J4A-17-PadA17)") (class "Default")
      (node (ref "J4") (pin "A17") (pinfunction "17_A17") (pintype "passive"))
    )
    (net (code "103") (name "unconnected-(J4A-18-PadA18)") (class "Default")
      (node (ref "J4") (pin "A18") (pinfunction "18_A18") (pintype "passive"))
    )
    (net (code "104") (name "unconnected-(J4A-19-PadA19)") (class "Default")
      (node (ref "J4") (pin "A19") (pinfunction "19_A19") (pintype "passive"))
    )
    (net (code "105") (name "unconnected-(J4A-20-PadA20)") (class "Default")
      (node (ref "J4") (pin "A20") (pinfunction "20_A20") (pintype "passive"))
    )
    (net (code "106") (name "unconnected-(J4A-21-PadA21)") (class "Default")
      (node (ref "J4") (pin "A21") (pinfunction "21_A21") (pintype "passive"))
    )
    (net (code "107") (name "unconnected-(J4A-22-PadA22)") (class "Default")
      (node (ref "J4") (pin "A22") (pinfunction "22_A22") (pintype "passive"))
    )
    (net (code "108") (name "unconnected-(J4A-23-PadA23)") (class "Default")
      (node (ref "J4") (pin "A23") (pinfunction "23_A23") (pintype "passive"))
    )
    (net (code "109") (name "unconnected-(J4A-24-PadA24)") (class "Default")
      (node (ref "J4") (pin "A24") (pinfunction "24_A24") (pintype "passive"))
    )
    (net (code "110") (name "unconnected-(J4A-25-PadA25)") (class "Default")
      (node (ref "J4") (pin "A25") (pinfunction "25_A25") (pintype "passive"))
    )
    (net (code "111") (name "unconnected-(J4A-26-PadA26)") (class "Default")
      (node (ref "J4") (pin "A26") (pinfunction "26_A26") (pintype "passive"))
    )
    (net (code "112") (name "unconnected-(J4A-27-PadA27)") (class "Default")
      (node (ref "J4") (pin "A27") (pinfunction "27_A27") (pintype "passive"))
    )
    (net (code "113") (name "unconnected-(J4A-28-PadA28)") (class "Default")
      (node (ref "J4") (pin "A28") (pinfunction "28_A28") (pintype "passive"))
    )
    (net (code "114") (name "unconnected-(J4A-29-PadA29)") (class "Default")
      (node (ref "J4") (pin "A29") (pinfunction "29_A29") (pintype "passive"))
    )
    (net (code "115") (name "unconnected-(J4A-30-PadA30)") (class "Default")
      (node (ref "J4") (pin "A30") (pinfunction "30_A30") (pintype "passive"))
    )
    (net (code "116") (name "unconnected-(J4A-31-PadA31)") (class "Default")
      (node (ref "J4") (pin "A31") (pinfunction "31_A31") (pintype "passive"))
    )
    (net (code "117") (name "unconnected-(J4A-32-PadA32)") (class "Default")
      (node (ref "J4") (pin "A32") (pinfunction "32_A32") (pintype "passive"))
    )
    (net (code "118") (name "unconnected-(J4B-1-PadB1)") (class "Default")
      (node (ref "J4") (pin "B1") (pinfunction "1_B1") (pintype "passive"))
    )
    (net (code "119") (name "unconnected-(J4B-2-PadB2)") (class "Default")
      (node (ref "J4") (pin "B2") (pinfunction "2_B2") (pintype "passive"))
    )
    (net (code "120") (name "unconnected-(J4B-3-PadB3)") (class "Default")
      (node (ref "J4") (pin "B3") (pinfunction "3_B3") (pintype "passive"))
    )
    (net (code "121") (name "unconnected-(J4B-4-PadB4)") (class "Default")
      (node (ref "J4") (pin "B4") (pinfunction "4_B4") (pintype "passive"))
    )
    (net (code "122") (name "unconnected-(J4B-5-PadB5)") (class "Default")
      (node (ref "J4") (pin "B5") (pinfunction "5_B5") (pintype "passive"))
    )
    (net (code "123") (name "unconnected-(J4B-6-PadB6)") (class "Default")
      (node (ref "J4") (pin "B6") (pinfunction "6_B6") (pintype "passive"))
    )
    (net (code "124") (name "unconnected-(J4B-7-PadB7)") (class "Default")
      (node (ref "J4") (pin "B7") (pinfunction "7_B7") (pintype "passive"))
    )
    (net (code "125") (name "unconnected-(J4B-8-PadB8)") (class "Default")
      (node (ref "J4") (pin "B8") (pinfunction "8_B8") (pintype "passive"))
    )
    (net (code "126") (name "unconnected-(J4B-9-PadB9)") (class "Default")
      (node (ref "J4") (pin "B9") (pinfunction "9_B9") (pintype "passive"))
    )
    (net (code "127") (name "unconnected-(J4B-10-PadB10)") (class "Default")
      (node (ref "J4") (pin "B10") (pinfunction "10_B10") (pintype "passive"))
    )
    (net (code "128") (name "unconnected-(J4B-11-PadB11)") (class "Default")
      (node (ref "J4") (pin "B11") (pinfunction "11_B11") (pintype "passive"))
    )
    (net (code "129") (name "unconnected-(J4B-12-PadB12)") (class "Default")
      (node (ref "J4") (pin "B12") (pinfunction "12_B12") (pintype "passive"))
    )
    (net (code "130") (name "unconnected-(J4B-13-PadB13)") (class "Default")
      (node (ref "J4") (pin "B13") (pinfunction "13_B13") (pintype "passive"))
    )
    (net (code "131") (name "unconnected-(J4B-14-PadB14)") (class "Default")
      (node (ref "J4") (pin "B14") (pinfunction "14_B14") (pintype "passive"))
    )
    (net (code "132") (name "unconnected-(J4B-15-PadB15)") (class "Default")
      (node (ref "J4") (pin "B15") (pinfunction "15_B15") (pintype "passive"))
    )
    (net (code "133") (name "unconnected-(J4B-16-PadB16)") (class "Default")
      (node (ref "J4") (pin "B16") (pinfunction "16_B16") (pintype "passive"))
    )
    (net (code "134") (name "unconnected-(J4B-17-PadB17)") (class "Default")
      (node (ref "J4") (pin "B17") (pinfunction "17_B17") (pintype "passive"))
    )
    (net (code "135") (name "unconnected-(J4B-18-PadB18)") (class "Default")
      (node (ref "J4") (pin "B18") (pinfunction "18_B18") (pintype "passive"))
    )
    (net (code "136") (name "unconnected-(J4B-19-PadB19)") (class "Default")
      (node (ref "J4") (pin "B19") (pinfunction "19_B19") (pintype "passive"))
    )
    (net (code "137") (name "unconnected-(J4B-20-PadB20)") (class "Default")
      (node (ref "J4") (pin "B20") (pinfunction "20_B20") (pintype "passive"))
    )
    (net (code "138") (name "unconnected-(J4B-21-PadB21)") (class "Default")
      (node (ref "J4") (pin "B21") (pinfunction "21_B21") (pintype "passive"))
    )
    (net (code "139") (name "unconnected-(J4B-22-PadB22)") (class "Default")
      (node (ref "J4") (pin "B22") (pinfunction "22_B22") (pintype "passive"))
    )
    (net (code "140") (name "unconnected-(J4B-23-PadB23)") (class "Default")
      (node (ref "J4") (pin "B23") (pinfunction "23_B23") (pintype "passive"))
    )
    (net (code "141") (name "unconnected-(J4B-24-PadB24)") (class "Default")
      (node (ref "J4") (pin "B24") (pinfunction "24_B24") (pintype "passive"))
    )
    (net (code "142") (name "unconnected-(J4B-25-PadB25)") (class "Default")
      (node (ref "J4") (pin "B25") (pinfunction "25_B25") (pintype "passive"))
    )
    (net (code "143") (name "unconnected-(J4B-26-PadB26)") (class "Default")
      (node (ref "J4") (pin "B26") (pinfunction "26_B26") (pintype "passive"))
    )
    (net (code "144") (name "unconnected-(J4B-27-PadB27)") (class "Default")
      (node (ref "J4") (pin "B27") (pinfunction "27_B27") (pintype "passive"))
    )
    (net (code "145") (name "unconnected-(J4B-28-PadB28)") (class "Default")
      (node (ref "J4") (pin "B28") (pinfunction "28_B28") (pintype "passive"))
    )
    (net (code "146") (name "unconnected-(J4B-29-PadB29)") (class "Default")
      (node (ref "J4") (pin "B29") (pinfunction "29_B29") (pintype "passive"))
    )
    (net (code "147") (name "unconnected-(J4B-30-PadB30)") (class "Default")
      (node (ref "J4") (pin "B30") (pinfunction "30_B30") (pintype "passive"))
    )
    (net (code "148") (name "unconnected-(J4B-31-PadB31)") (class "Default")
      (node (ref "J4") (pin "B31") (pinfunction "31_B31") (pintype "passive"))
    )
    (net (code "149") (name "unconnected-(J4B-32-PadB32)") (class "Default")
      (node (ref "J4") (pin "B32") (pinfunction "32_B32") (pintype "passive"))
    )
    (net (code "150") (name "unconnected-(J4C-1-PadC1)") (class "Default")
      (node (ref "J4") (pin "C1") (pinfunction "1_C1") (pintype "passive"))
    )
    (net (code "151") (name "unconnected-(J4C-2-PadC2)") (class "Default")
      (node (ref "J4") (pin "C2") (pinfunction "2_C2") (pintype "passive"))
    )
    (net (code "152") (name "unconnected-(J4C-3-PadC3)") (class "Default")
      (node (ref "J4") (pin "C3") (pinfunction "3_C3") (pintype "passive"))
    )
    (net (code "153") (name "unconnected-(J4C-4-PadC4)") (class "Default")
      (node (ref "J4") (pin "C4") (pinfunction "4_C4") (pintype "passive"))
    )
    (net (code "154") (name "unconnected-(J4C-5-PadC5)") (class "Default")
      (node (ref "J4") (pin "C5") (pinfunction "5_C5") (pintype "passive"))
    )
    (net (code "155") (name "unconnected-(J4C-6-PadC6)") (class "Default")
      (node (ref "J4") (pin "C6") (pinfunction "6_C6") (pintype "passive"))
    )
    (net (code "156") (name "unconnected-(J4C-7-PadC7)") (class "Default")
      (node (ref "J4") (pin "C7") (pinfunction "7_C7") (pintype "passive"))
    )
    (net (code "157") (name "unconnected-(J4C-8-PadC8)") (class "Default")
      (node (ref "J4") (pin "C8") (pinfunction "8_C8") (pintype "passive"))
    )
    (net (code "158") (name "unconnected-(J4C-9-PadC9)") (class "Default")
      (node (ref "J4") (pin "C9") (pinfunction "9_C9") (pintype "passive"))
    )
    (net (code "159") (name "unconnected-(J4C-10-PadC10)") (class "Default")
      (node (ref "J4") (pin "C10") (pinfunction "10_C10") (pintype "passive"))
    )
    (net (code "160") (name "unconnected-(J4C-11-PadC11)") (class "Default")
      (node (ref "J4") (pin "C11") (pinfunction "11_C11") (pintype "passive"))
    )
    (net (code "161") (name "unconnected-(J4C-12-PadC12)") (class "Default")
      (node (ref "J4") (pin "C12") (pinfunction "12_C12") (pintype "passive"))
    )
    (net (code "162") (name "unconnected-(J4C-13-PadC13)") (class "Default")
      (node (ref "J4") (pin "C13") (pinfunction "13_C13") (pintype "passive"))
    )
    (net (code "163") (name "unconnected-(J4C-14-PadC14)") (class "Default")
      (node (ref "J4") (pin "C14") (pinfunction "14_C14") (pintype "passive"))
    )
    (net (code "164") (name "unconnected-(J4C-15-PadC15)") (class "Default")
      (node (ref "J4") (pin "C15") (pinfunction "15_C15") (pintype "passive"))
    )
    (net (code "165") (name "unconnected-(J4C-16-PadC16)") (class "Default")
      (node (ref "J4") (pin "C16") (pinfunction "16_C16") (pintype "passive"))
    )
    (net (code "166") (name "unconnected-(J4C-17-PadC17)") (class "Default")
      (node (ref "J4") (pin "C17") (pinfunction "17_C17") (pintype "passive"))
    )
    (net (code "167") (name "unconnected-(J4C-18-PadC18)") (class "Default")
      (node (ref "J4") (pin "C18") (pinfunction "18_C18") (pintype "passive"))
    )
    (net (code "168") (name "unconnected-(J4C-19-PadC19)") (class "Default")
      (node (ref "J4") (pin "C19") (pinfunction "19_C19") (pintype "passive"))
    )
    (net (code "169") (name "unconnected-(J4C-20-PadC20)") (class "Default")
      (node (ref "J4") (pin "C20") (pinfunction "20_C20") (pintype "passive"))
    )
    (net (code "170") (name "unconnected-(J4C-21-PadC21)") (class "Default")
      (node (ref "J4") (pin "C21") (pinfunction "21_C21") (pintype "passive"))
    )
    (net (code "171") (name "unconnected-(J4C-22-PadC22)") (class "Default")
      (node (ref "J4") (pin "C22") (pinfunction "22_C22") (pintype "passive"))
    )
    (net (code "172") (name "unconnected-(J4C-23-PadC23)") (class "Default")
      (node (ref "J4") (pin "C23") (pinfunction "23_C23") (pintype "passive"))
    )
    (net (code "173") (name "unconnected-(J4C-24-PadC24)") (class "Default")
      (node (ref "J4") (pin "C24") (pinfunction "24_C24") (pintype "passive"))
    )
    (net (code "174") (name "unconnected-(J4C-25-PadC25)") (class "Default")
      (node (ref "J4") (pin "C25") (pinfunction "25_C25") (pintype "passive"))
    )
    (net (code "175") (name "unconnected-(J4C-26-PadC26)") (class "Default")
      (node (ref "J4") (pin "C26") (pinfunction "26_C26") (pintype "passive"))
    )
    (net (code "176") (name "unconnected-(J4C-27-PadC27)") (class "Default")
      (node (ref "J4") (pin "C27") (pinfunction "27_C27") (pintype "passive"))
    )
    (net (code "177") (name "unconnected-(J4C-28-PadC28)") (class "Default")
      (node (ref "J4") (pin "C28") (pinfunction "28_C28") (pintype "passive"))
    )
    (net (code "178") (name "unconnected-(J4C-29-PadC29)") (class "Default")
      (node (ref "J4") (pin "C29") (pinfunction "29_C29") (pintype "passive"))
    )
    (net (code "179") (name "unconnected-(J4C-30-PadC30)") (class "Default")
      (node (ref "J4") (pin "C30") (pinfunction "30_C30") (pintype "passive"))
    )
    (net (code "180") (name "unconnected-(J4C-31-PadC31)") (class "Default")
      (node (ref "J4") (pin "C31") (pinfunction "31_C31") (pintype "passive"))
    )
    (net (code "181") (name "unconnected-(J4C-32-PadC32)") (class "Default")
      (node (ref "J4") (pin "C32") (pinfunction "32_C32") (pintype "passive"))
    )
    (net (code "182") (name "unconnected-(RN1-Pad8)") (class "Default")
      (node (ref "RN1") (pin "8") (pinfunction "8_8") (pintype "passive"))
    )
    (net (code "183") (name "unconnected-(RN1-Pad9)") (class "Default")
      (node (ref "RN1") (pin "9") (pinfunction "9_9") (pintype "passive"))
    )
    (net (code "184") (name "unconnected-(RN2-Pad8)") (class "Default")
      (node (ref "RN2") (pin "8") (pinfunction "8_8") (pintype "passive"))
    )
    (net (code "185") (name "unconnected-(RN2-Pad9)") (class "Default")
      (node (ref "RN2") (pin "9") (pinfunction "9_9") (pintype "passive"))
    )
    (net (code "186") (name "unconnected-(USB-Pad1)") (class "Default")
      (node (ref "USB") (pin "1") (pinfunction "1_1") (pintype "passive"))
    )
    (net (code "187") (name "unconnected-(USB-Pad4)") (class "Default")
      (node (ref "USB") (pin "4") (pinfunction "4_4") (pintype "passive"))
    )
    (net (code "188") (name "unconnected-(USB-Pad6)") (class "Default")
      (node (ref "USB") (pin "6") (pinfunction "6_6") (pintype "passive"))
    )
    (net (code "189") (name "unconnected-(USB-Pad7)") (class "Default")
      (node (ref "USB") (pin "7") (pinfunction "7_7") (pintype "passive"))
    )
    (net (code "190") (name "unconnected-(USB-Pad8)") (class "Default")
      (node (ref "USB") (pin "8") (pinfunction "8_8") (pintype "passive"))
    )
    (net (code "191") (name "unconnected-(USB-Pad9)") (class "Default")
      (node (ref "USB") (pin "9") (pinfunction "9_9") (pintype "passive"))
    )
  )
)
